# Sheet1.net
KiCad netlist of a schematic drawn in Altium Designer
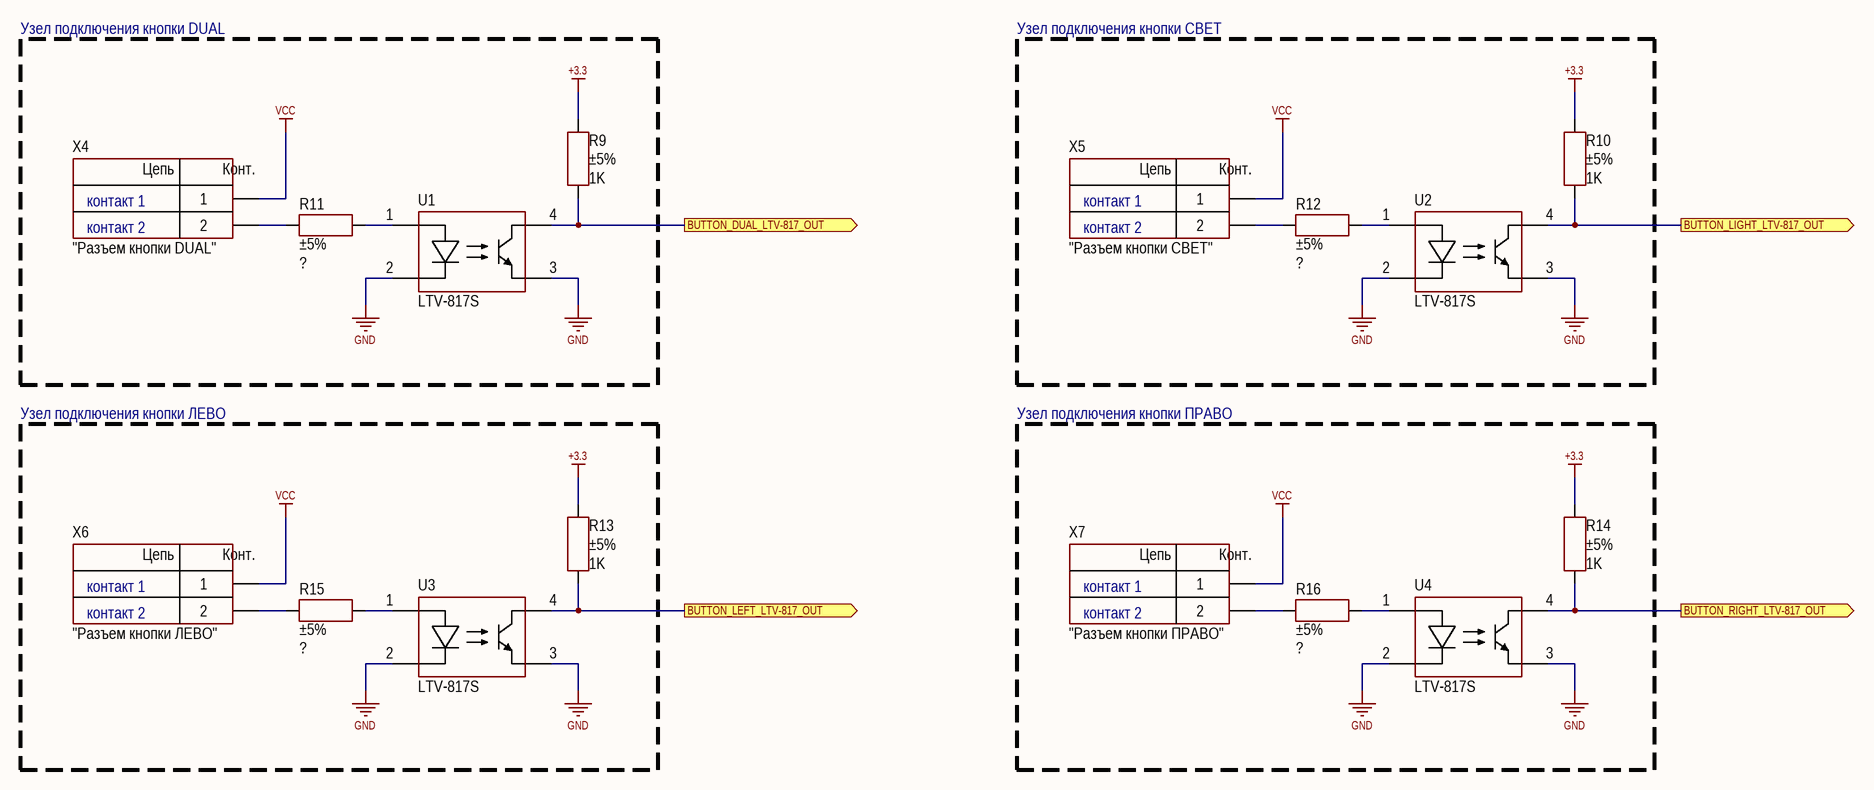
[diagram p0: Sheet1.SchDoc]

(export (version "E")
  (design (tool "Eeschema 10.0.6"))
  (components
    (comp (ref "R9")
      (value "1K")
      (footprint "RES: 0603")
      (fields
        (field (name "MANUFACTURER") "Yageo")
        (field (name "PARTNUMBER") "RC0603JR-07100RL")
        (field (name "VALUEMANUFACTURERPARTNUMBER") "Resistor film, 1K, ±5%, 0603, 0.1W, -55...+125°C")
        (field (name "TOLERANCE") "±5%")
      )
      (libsource (lib "") (part "Resistor_0603_1"))
    )
    (comp (ref "R10")
      (value "1K")
      (footprint "RES: 0603")
      (fields
        (field (name "MANUFACTURER") "Yageo")
        (field (name "PARTNUMBER") "RC0603JR-07100RL")
        (field (name "VALUEMANUFACTURERPARTNUMBER") "Resistor film, 1K, ±5%, 0603, 0.1W, -55...+125°C")
        (field (name "TOLERANCE") "±5%")
      )
      (libsource (lib "") (part "Resistor_0603_1"))
    )
    (comp (ref "R11")
      (value "?")
      (footprint "RES: 0603")
      (fields
        (field (name "MANUFACTURER") "Yageo")
        (field (name "PARTNUMBER") "RC0603JR-07100RL")
        (field (name "VALUEMANUFACTURERPARTNUMBER") "Resistor film, ?, ±5%, 0603, 0.1W, -55...+125°C")
        (field (name "TOLERANCE") "±5%")
      )
      (libsource (lib "resistor") (part "Resistor_0603"))
    )
    (comp (ref "R12")
      (value "?")
      (footprint "RES: 0603")
      (fields
        (field (name "MANUFACTURER") "Yageo")
        (field (name "PARTNUMBER") "RC0603JR-07100RL")
        (field (name "VALUEMANUFACTURERPARTNUMBER") "Resistor film, ?, ±5%, 0603, 0.1W, -55...+125°C")
        (field (name "TOLERANCE") "±5%")
      )
      (libsource (lib "resistor") (part "Resistor_0603"))
    )
    (comp (ref "R13")
      (value "1K")
      (footprint "RES: 0603")
      (fields
        (field (name "MANUFACTURER") "Yageo")
        (field (name "PARTNUMBER") "RC0603JR-07100RL")
        (field (name "VALUEMANUFACTURERPARTNUMBER") "Resistor film, 1K, ±5%, 0603, 0.1W, -55...+125°C")
        (field (name "TOLERANCE") "±5%")
      )
      (libsource (lib "") (part "Resistor_0603_1"))
    )
    (comp (ref "R14")
      (value "1K")
      (footprint "RES: 0603")
      (fields
        (field (name "MANUFACTURER") "Yageo")
        (field (name "PARTNUMBER") "RC0603JR-07100RL")
        (field (name "VALUEMANUFACTURERPARTNUMBER") "Resistor film, 1K, ±5%, 0603, 0.1W, -55...+125°C")
        (field (name "TOLERANCE") "±5%")
      )
      (libsource (lib "") (part "Resistor_0603_1"))
    )
    (comp (ref "R15")
      (value "?")
      (footprint "RES: 0603")
      (fields
        (field (name "MANUFACTURER") "Yageo")
        (field (name "PARTNUMBER") "RC0603JR-07100RL")
        (field (name "VALUEMANUFACTURERPARTNUMBER") "Resistor film, ?, ±5%, 0603, 0.1W, -55...+125°C")
        (field (name "TOLERANCE") "±5%")
      )
      (libsource (lib "resistor") (part "Resistor_0603"))
    )
    (comp (ref "R16")
      (value "?")
      (footprint "RES: 0603")
      (fields
        (field (name "MANUFACTURER") "Yageo")
        (field (name "PARTNUMBER") "RC0603JR-07100RL")
        (field (name "VALUEMANUFACTURERPARTNUMBER") "Resistor film, ?, ±5%, 0603, 0.1W, -55...+125°C")
        (field (name "TOLERANCE") "±5%")
      )
      (libsource (lib "resistor") (part "Resistor_0603"))
    )
    (comp (ref "U1")
      (value "~")
      (footprint "4-SMD")
      (description "Optoisolator")
      (fields
        (field (name "MANUFACTURER") "Lite-On")
        (field (name "VALUEMANUFACTURERPARTNUMBER") "IC optoisolator, 4µs/3µs, 5000Vrms, 35V, -40...+125°C, 4-SMD")
        (field (name "PARTNUMBER") "LTV-817S")
      )
      (libsource (lib "optoisolator") (part "LTV-817"))
    )
    (comp (ref "U2")
      (value "~")
      (footprint "4-SMD")
      (description "Optoisolator")
      (fields
        (field (name "MANUFACTURER") "Lite-On")
        (field (name "VALUEMANUFACTURERPARTNUMBER") "IC optoisolator, 4µs/3µs, 5000Vrms, 35V, -40...+125°C, 4-SMD")
        (field (name "PARTNUMBER") "LTV-817S")
      )
      (libsource (lib "optoisolator") (part "LTV-817"))
    )
    (comp (ref "U3")
      (value "~")
      (footprint "4-SMD")
      (description "Optoisolator")
      (fields
        (field (name "MANUFACTURER") "Lite-On")
        (field (name "VALUEMANUFACTURERPARTNUMBER") "IC optoisolator, 4µs/3µs, 5000Vrms, 35V, -40...+125°C, 4-SMD")
        (field (name "PARTNUMBER") "LTV-817S")
      )
      (libsource (lib "optoisolator") (part "LTV-817"))
    )
    (comp (ref "U4")
      (value "~")
      (footprint "4-SMD")
      (description "Optoisolator")
      (fields
        (field (name "MANUFACTURER") "Lite-On")
        (field (name "VALUEMANUFACTURERPARTNUMBER") "IC optoisolator, 4µs/3µs, 5000Vrms, 35V, -40...+125°C, 4-SMD")
        (field (name "PARTNUMBER") "LTV-817S")
      )
      (libsource (lib "optoisolator") (part "LTV-817"))
    )
    (comp (ref "X4")
      (value "~")
      (footprint "CON: DG350-3.5-02P")
      (fields
        (field (name "MANUFACTURER") "Degson")
        (field (name "VALUEMANUFACTURERPARTNUMBER") "Terminal connector, 2pin, 3.5mm, 300VAC, 10A")
        (field (name "PARTNUMBER") "DG350-3.5-02P-14")
        (field (name "COMMENTTEXT") "\"Разъем кнопки DUAL\"")
      )
      (libsource (lib "connector") (part "Connector_terminal_2pin"))
    )
    (comp (ref "X5")
      (value "~")
      (footprint "CON: DG350-3.5-02P")
      (fields
        (field (name "MANUFACTURER") "Degson")
        (field (name "VALUEMANUFACTURERPARTNUMBER") "Terminal connector, 2pin, 3.5mm, 300VAC, 10A")
        (field (name "PARTNUMBER") "DG350-3.5-02P-14")
        (field (name "COMMENTTEXT") "\"Разъем кнопки СВЕТ\"")
      )
      (libsource (lib "connector") (part "Connector_terminal_2pin"))
    )
    (comp (ref "X6")
      (value "~")
      (footprint "CON: DG350-3.5-02P")
      (fields
        (field (name "MANUFACTURER") "Degson")
        (field (name "VALUEMANUFACTURERPARTNUMBER") "Terminal connector, 2pin, 3.5mm, 300VAC, 10A")
        (field (name "PARTNUMBER") "DG350-3.5-02P-14")
        (field (name "COMMENTTEXT") "\"Разъем кнопки ЛЕВО\"")
      )
      (libsource (lib "connector") (part "Connector_terminal_2pin"))
    )
    (comp (ref "X7")
      (value "~")
      (footprint "CON: DG350-3.5-02P")
      (fields
        (field (name "MANUFACTURER") "Degson")
        (field (name "VALUEMANUFACTURERPARTNUMBER") "Terminal connector, 2pin, 3.5mm, 300VAC, 10A")
        (field (name "PARTNUMBER") "DG350-3.5-02P-14")
        (field (name "COMMENTTEXT") "\"Разъем кнопки ПРАВО\"")
      )
      (libsource (lib "connector") (part "Connector_terminal_2pin"))
    )
  )
  (nets
    (net (code "1") (name "+3.3") (class "Default")
      (node (ref "R10") (pin "2") (pinfunction "2_2") (pintype "passive"))
      (node (ref "R13") (pin "2") (pinfunction "2_2") (pintype "passive"))
      (node (ref "R14") (pin "2") (pinfunction "2_2") (pintype "passive"))
      (node (ref "R9") (pin "2") (pinfunction "2_2") (pintype "passive"))
    )
    (net (code "2") (name "/BUTTON_DUAL_LTV-817_OUT") (class "Default")
      (node (ref "R9") (pin "1") (pinfunction "1_1") (pintype "passive"))
      (node (ref "U1") (pin "4") (pinfunction "C_4") (pintype "passive"))
    )
    (net (code "3") (name "/BUTTON_LEFT_LTV-817_OUT") (class "Default")
      (node (ref "R13") (pin "1") (pinfunction "1_1") (pintype "passive"))
      (node (ref "U3") (pin "4") (pinfunction "C_4") (pintype "passive"))
    )
    (net (code "4") (name "/BUTTON_LIGHT_LTV-817_OUT") (class "Default")
      (node (ref "R10") (pin "1") (pinfunction "1_1") (pintype "passive"))
      (node (ref "U2") (pin "4") (pinfunction "C_4") (pintype "passive"))
    )
    (net (code "5") (name "/BUTTON_RIGHT_LTV-817_OUT") (class "Default")
      (node (ref "R14") (pin "1") (pinfunction "1_1") (pintype "passive"))
      (node (ref "U4") (pin "4") (pinfunction "C_4") (pintype "passive"))
    )
    (net (code "6") (name "GND") (class "Default")
      (node (ref "U1") (pin "2") (pinfunction "C_2") (pintype "passive"))
      (node (ref "U1") (pin "3") (pinfunction "E_3") (pintype "passive"))
      (node (ref "U2") (pin "2") (pinfunction "C_2") (pintype "passive"))
      (node (ref "U2") (pin "3") (pinfunction "E_3") (pintype "passive"))
      (node (ref "U3") (pin "2") (pinfunction "C_2") (pintype "passive"))
      (node (ref "U3") (pin "3") (pinfunction "E_3") (pintype "passive"))
      (node (ref "U4") (pin "2") (pinfunction "C_2") (pintype "passive"))
      (node (ref "U4") (pin "3") (pinfunction "E_3") (pintype "passive"))
    )
    (net (code "7") (name "Net-(R11-Pad1)") (class "Default")
      (node (ref "R11") (pin "1") (pinfunction "1_1") (pintype "passive"))
      (node (ref "X4") (pin "2") (pinfunction "2_2") (pintype "passive"))
    )
    (net (code "8") (name "Net-(R12-Pad1)") (class "Default")
      (node (ref "R12") (pin "1") (pinfunction "1_1") (pintype "passive"))
      (node (ref "X5") (pin "2") (pinfunction "2_2") (pintype "passive"))
    )
    (net (code "9") (name "Net-(R15-Pad1)") (class "Default")
      (node (ref "R15") (pin "1") (pinfunction "1_1") (pintype "passive"))
      (node (ref "X6") (pin "2") (pinfunction "2_2") (pintype "passive"))
    )
    (net (code "10") (name "Net-(R16-Pad1)") (class "Default")
      (node (ref "R16") (pin "1") (pinfunction "1_1") (pintype "passive"))
      (node (ref "X7") (pin "2") (pinfunction "2_2") (pintype "passive"))
    )
    (net (code "11") (name "Net-(U1-A)") (class "Default")
      (node (ref "R11") (pin "2") (pinfunction "2_2") (pintype "passive"))
      (node (ref "U1") (pin "1") (pinfunction "A_1") (pintype "passive"))
    )
    (net (code "12") (name "Net-(U2-A)") (class "Default")
      (node (ref "R12") (pin "2") (pinfunction "2_2") (pintype "passive"))
      (node (ref "U2") (pin "1") (pinfunction "A_1") (pintype "passive"))
    )
    (net (code "13") (name "Net-(U3-A)") (class "Default")
      (node (ref "R15") (pin "2") (pinfunction "2_2") (pintype "passive"))
      (node (ref "U3") (pin "1") (pinfunction "A_1") (pintype "passive"))
    )
    (net (code "14") (name "Net-(U4-A)") (class "Default")
      (node (ref "R16") (pin "2") (pinfunction "2_2") (pintype "passive"))
      (node (ref "U4") (pin "1") (pinfunction "A_1") (pintype "passive"))
    )
    (net (code "15") (name "VCC") (class "Default")
      (node (ref "X4") (pin "1") (pinfunction "1_1") (pintype "passive"))
      (node (ref "X5") (pin "1") (pinfunction "1_1") (pintype "passive"))
      (node (ref "X6") (pin "1") (pinfunction "1_1") (pintype "passive"))
      (node (ref "X7") (pin "1") (pinfunction "1_1") (pintype "passive"))
    )
  )
)
